# Aerator_slave.net
KiCad netlist of a schematic drawn in EAGLE
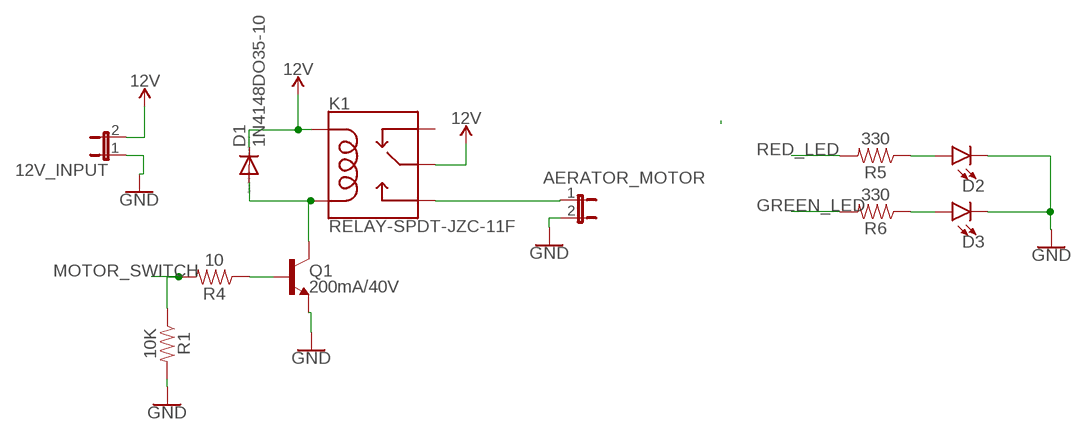
[diagram p0: schematic, sheet 1]

(export (version "E")
  (design (tool "Eeschema 10.0.6"))
  (components
    (comp (ref "12V_INPUT")
      (value "JUMPER-2PTH")
      (footprint "eagle-import:1X02")
      (libsource (lib "eagle-import") (part "JUMPER-2PTH"))
    )
    (comp (ref "AERATOR_MOTOR")
      (value "JUMPER-2PTH")
      (footprint "eagle-import:1X02")
      (libsource (lib "eagle-import") (part "JUMPER-2PTH"))
    )
    (comp (ref "D1")
      (value "1N4148DO35-10")
      (footprint "eagle-import:DO35-10")
      (libsource (lib "eagle-import") (part "1N4148DO35-10"))
    )
    (comp (ref "D2")
      (value "LED5MM")
      (footprint "eagle-import:LED_5MM")
      (libsource (lib "eagle-import") (part "LED5MM"))
    )
    (comp (ref "D3")
      (value "LED5MM")
      (footprint "eagle-import:LED_5MM")
      (libsource (lib "eagle-import") (part "LED5MM"))
    )
    (comp (ref "K1")
      (value "RELAY-SPDT-JZC-11F")
      (footprint "eagle-import:RELAY-JZC")
      (libsource (lib "eagle-import") (part "RELAY-SPDT-JZC-11F"))
    )
    (comp (ref "Q1")
      (value "200mA/40V")
      (footprint "eagle-import:TO-92")
      (libsource (lib "eagle-import") (part "TRANS_NPN-2N3904"))
    )
    (comp (ref "R1")
      (value "10K")
      (footprint "eagle-import:AXIAL-0.3")
      (libsource (lib "eagle-import") (part "10OHM-HORIZ-1/4W-1%"))
    )
    (comp (ref "R4")
      (value "10")
      (footprint "eagle-import:AXIAL-0.3")
      (libsource (lib "eagle-import") (part "10OHM-HORIZ-1/4W-1%"))
    )
    (comp (ref "R5")
      (value "330")
      (footprint "eagle-import:AXIAL-0.3")
      (libsource (lib "eagle-import") (part "330OHM-HORIZ-1/10W-5%"))
    )
    (comp (ref "R6")
      (value "330")
      (footprint "eagle-import:AXIAL-0.3")
      (libsource (lib "eagle-import") (part "330OHM-HORIZ-1/10W-5%"))
    )
  )
  (nets
    (net (code "1") (name "/GREEN_LED") (class "Default")
      (node (ref "R6") (pin "P$2") (pinfunction "2_P$2") (pintype "passive"))
    )
    (net (code "2") (name "/MOTOR_SWITCH") (class "Default")
      (node (ref "R1") (pin "P$1") (pinfunction "1_P$1") (pintype "passive"))
      (node (ref "R4") (pin "P$2") (pinfunction "2_P$2") (pintype "passive"))
    )
    (net (code "3") (name "/RED_LED") (class "Default")
      (node (ref "R5") (pin "P$2") (pinfunction "2_P$2") (pintype "passive"))
    )
    (net (code "4") (name "12V") (class "Default")
      (node (ref "12V_INPUT") (pin "2") (pinfunction "2_2") (pintype "passive"))
      (node (ref "D1") (pin "C") (pinfunction "C_C") (pintype "passive"))
      (node (ref "K1") (pin "4") (pinfunction "MAIN_4") (pintype "bidirectional"))
      (node (ref "K1") (pin "5") (pinfunction "COIL1_5") (pintype "bidirectional"))
    )
    (net (code "5") (name "GND") (class "Default")
      (node (ref "12V_INPUT") (pin "1") (pinfunction "1_1") (pintype "passive"))
      (node (ref "AERATOR_MOTOR") (pin "2") (pinfunction "2_2") (pintype "passive"))
      (node (ref "D2") (pin "K") (pinfunction "C_K") (pintype "passive"))
      (node (ref "D3") (pin "K") (pinfunction "C_K") (pintype "passive"))
      (node (ref "Q1") (pin "1") (pinfunction "E_1") (pintype "passive"))
      (node (ref "R1") (pin "P$2") (pinfunction "2_P$2") (pintype "passive"))
    )
    (net (code "6") (name "Net-(K1-COIL2)") (class "Default")
      (node (ref "D1") (pin "A") (pinfunction "A_A") (pintype "passive"))
      (node (ref "K1") (pin "1") (pinfunction "COIL2_1") (pintype "bidirectional"))
      (node (ref "Q1") (pin "3") (pinfunction "C_3") (pintype "passive"))
    )
    (net (code "7") (name "Net-(K1-NO)") (class "Default")
      (node (ref "AERATOR_MOTOR") (pin "1") (pinfunction "1_1") (pintype "passive"))
      (node (ref "K1") (pin "3") (pinfunction "NO_3") (pintype "bidirectional"))
    )
    (net (code "8") (name "Net-(Q1-B)") (class "Default")
      (node (ref "Q1") (pin "2") (pinfunction "B_2") (pintype "passive"))
      (node (ref "R4") (pin "P$1") (pinfunction "1_P$1") (pintype "passive"))
    )
    (net (code "9") (name "Net-(R5-1)") (class "Default")
      (node (ref "D2") (pin "A") (pinfunction "A_A") (pintype "passive"))
      (node (ref "R5") (pin "P$1") (pinfunction "1_P$1") (pintype "passive"))
    )
    (net (code "10") (name "Net-(R6-1)") (class "Default")
      (node (ref "D3") (pin "A") (pinfunction "A_A") (pintype "passive"))
      (node (ref "R6") (pin "P$1") (pinfunction "1_P$1") (pintype "passive"))
    )
    (net (code "11") (name "unconnected-(K1-NC-Pad2)") (class "Default")
      (node (ref "K1") (pin "2") (pinfunction "NC_2") (pintype "bidirectional"))
    )
  )
)
